# ESP32-Cam.net
KiCad netlist of a schematic drawn in Altium Designer
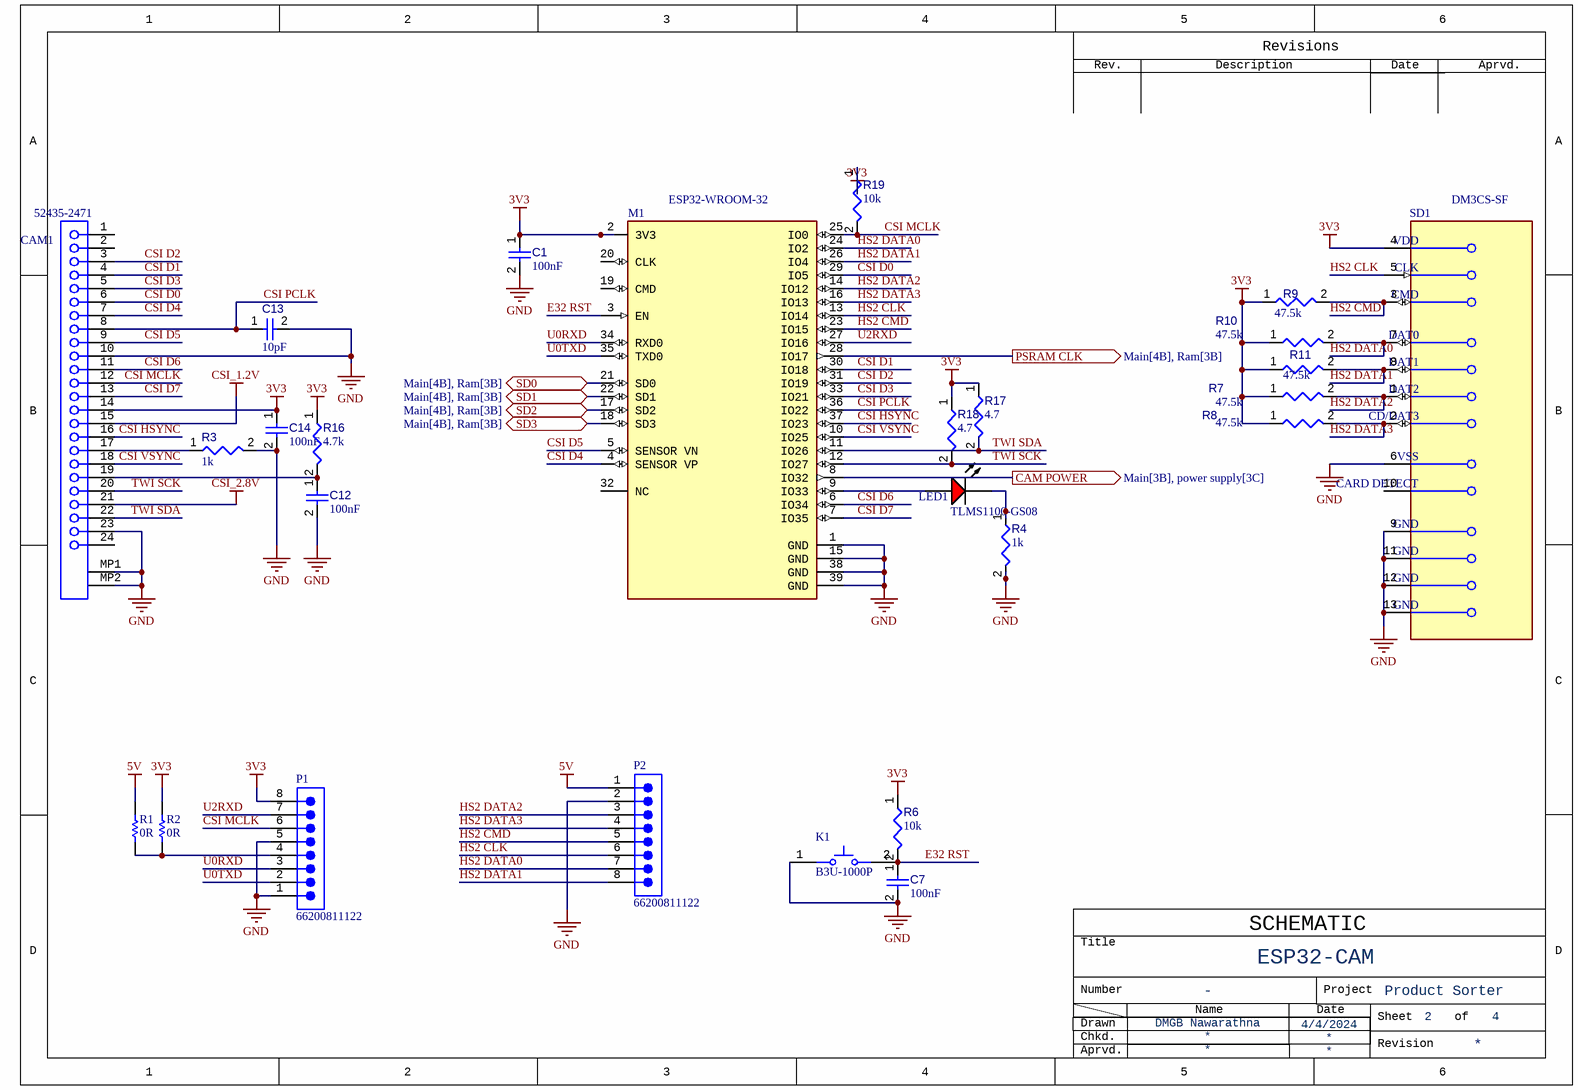
[diagram p0: ESP32-Cam.SchDoc]

(export (version "E")
  (design (tool "Eeschema 10.0.6"))
  (components
    (comp (ref "C1")
      (value "100nF")
      (footprint "CAPC1005X56X25LL10T15")
      (description "Chip Capacitor, 0.1 uF, +/- 5%, 16 V, 0402 (1005 Metric)")
      (fields (field (name "TOLERANCE") "5%") (field (name "Comment") "Capacitor 0.1 uF +/- 5% 16 V 0402"))
      (libsource (lib "Bimsara Nawarathna") (part "CAP-NP-2"))
    )
    (comp (ref "C7")
      (value "100nF")
      (footprint "CAPC1005X56X25LL10T15")
      (description "Chip Capacitor, 0.1 uF, +/- 5%, 16 V, 0402 (1005 Metric)")
      (fields (field (name "TOLERANCE") "5%") (field (name "Comment") "Capacitor 0.1 uF +/- 5% 16 V 0402"))
      (libsource (lib "Bimsara Nawarathna") (part "CAP-NP-2"))
    )
    (comp (ref "C12")
      (value "100nF")
      (footprint "CAPC1005X56X25LL10T15")
      (description "Chip Capacitor, 0.1 uF, +/- 5%, 16 V, 0402 (1005 Metric)")
      (fields (field (name "TOLERANCE") "5%") (field (name "Comment") "Capacitor 0.1 uF +/- 5% 16 V 0402"))
      (libsource (lib "Bimsara Nawarathna") (part "CAP-NP-2"))
    )
    (comp (ref "C13")
      (value "10pF")
      (footprint "CAPC1005X55X25ML05T05")
      (description "Chip Capacitor, 10 pF, +/- 5%, 50 V, 0402 (1005 Metric)")
      (fields (field (name "TOLERANCE") "5%") (field (name "Comment") "Capacitor 10 pF +/- 5% 50 V 0402"))
      (libsource (lib "Bimsara Nawarathna") (part "CAP-NP-2"))
    )
    (comp (ref "C14")
      (value "100nF")
      (footprint "CAPC1005X56X25LL10T15")
      (description "Chip Capacitor, 0.1 uF, +/- 5%, 16 V, 0402 (1005 Metric)")
      (fields (field (name "TOLERANCE") "5%") (field (name "Comment") "Capacitor 0.1 uF +/- 5% 16 V 0402"))
      (libsource (lib "Bimsara Nawarathna") (part "CAP-NP-2"))
    )
    (comp (ref "CAM1")
      (value "52435-2471")
      (footprint "MOLX-52435-2471")
      (fields (field (name "MANUFACTURER") "Molex"))
      (libsource (lib "Altium Content Vault") (part "MOLX-52435-2471"))
    )
    (comp (ref "K1")
      (value "B3U-1000P")
      (footprint "OMRON-B3U-1000_V")
      (description "Tactile Switch, SPST-NO, 0.05 A, 12 V, -25 to 70 degC, 2-Pin SMD, RoHS, Tape and Reel")
      (fields (field (name "MANUFACTURER") "Omron Electronic Components"))
      (libsource (lib "Bimsara Nawarathna") (part "SW-SPST-NO-2"))
    )
    (comp (ref "LED1")
      (value "TLMS1100-GS08")
      (footprint "VISH-TLMX1100_V")
      (description "Red Led, 20mA, 2.1 V, -40 to 100 degC, 2-Pin SMD (0603), RoHS, Tape and Reel")
      (fields (field (name "MANUFACTURER") "Vishay Semiconductor") (field (name "POWER") "90mW"))
      (libsource (lib "Bimsara Nawarathna") (part "LED-RED-AK-2"))
    )
    (comp (ref "M1")
      (value "ESP32-WROOM-32")
      (footprint "FP-ESP32-WROOM-32-MFG")
      (description "RX TXRX MOD WIFI SURFACE MOUNT")
      (libsource (lib "Altium Content Vault") (part "ee866abf0b6c51247b7f5cdebf2f250"))
    )
    (comp (ref "P1")
      (value "66200811122")
      (footprint "66200811122")
      (libsource (lib "Altium Content Vault") (part "Header_Male_1R_08P"))
    )
    (comp (ref "P2")
      (value "66200811122")
      (footprint "66200811122")
      (libsource (lib "Altium Content Vault") (part "Header_Male_1R_08P"))
    )
    (comp (ref "R1")
      (value "0R")
      (footprint "RESC1005X40X25ML05T10")
      (description "Chip Resistor, 0 Ohm, 0.063 W, -55 to 155 degC, 0402 (1005 Metric)")
      (fields (field (name "POWER") "63mW") (field (name "Comment") "Resistor 0R 0402 63 mW"))
      (libsource (lib "") (part "RES-2_1"))
    )
    (comp (ref "R2")
      (value "0R")
      (footprint "RESC1005X40X25ML05T10")
      (description "Chip Resistor, 0 Ohm, 0.063 W, -55 to 155 degC, 0402 (1005 Metric)")
      (fields (field (name "POWER") "63mW") (field (name "Comment") "Resistor 0R 0402 63 mW"))
      (libsource (lib "") (part "RES-2_1"))
    )
    (comp (ref "R3")
      (value "1k")
      (footprint "RESC0805(2012)_L")
      (description "Chip Resistor, 1 kOhms, +/-5%, 125 mW, -55 to 155 degC, 0805")
      (fields (field (name "TOLERANCE") "5%") (field (name "POWER") "125mW"))
      (libsource (lib "Bimsara Nawarathna") (part "RES-2"))
    )
    (comp (ref "R4")
      (value "1k")
      (footprint "RESC0805(2012)_L")
      (description "Chip Resistor, 1 kOhms, +/-5%, 125 mW, -55 to 155 degC, 0805")
      (fields (field (name "TOLERANCE") "5%") (field (name "POWER") "125mW"))
      (libsource (lib "Bimsara Nawarathna") (part "RES-2"))
    )
    (comp (ref "R6")
      (value "10k")
      (footprint "RESC0402(1005)_L")
      (description "Chip Resistor, 10 kOhms, +/-1 %, 63 mW, -55 to 125 degC, 0402")
      (fields (field (name "POWER") "63mW") (field (name "TOLERANCE") "1%"))
      (libsource (lib "Bimsara Nawarathna") (part "RES-2"))
    )
    (comp (ref "R7")
      (value "47.5k")
      (footprint "RESC0402(1005)_L")
      (description "Chip Resistor, 47,5 kOhms, +/-1 %, 63 mW, -55 to 155 degC, 0402")
      (fields (field (name "POWER") "63mW") (field (name "TOLERANCE") "1%"))
      (libsource (lib "Bimsara Nawarathna") (part "RES-2"))
    )
    (comp (ref "R8")
      (value "47.5k")
      (footprint "RESC0402(1005)_L")
      (description "Chip Resistor, 47,5 kOhms, +/-1 %, 63 mW, -55 to 155 degC, 0402")
      (fields (field (name "POWER") "63mW") (field (name "TOLERANCE") "1%"))
      (libsource (lib "Bimsara Nawarathna") (part "RES-2"))
    )
    (comp (ref "R9")
      (value "47.5k")
      (footprint "RESC0402(1005)_L")
      (description "Chip Resistor, 47,5 kOhms, +/-1 %, 63 mW, -55 to 155 degC, 0402")
      (fields (field (name "POWER") "63mW") (field (name "TOLERANCE") "1%"))
      (libsource (lib "Bimsara Nawarathna") (part "RES-2"))
    )
    (comp (ref "R10")
      (value "47.5k")
      (footprint "RESC0402(1005)_L")
      (description "Chip Resistor, 47,5 kOhms, +/-1 %, 63 mW, -55 to 155 degC, 0402")
      (fields (field (name "POWER") "63mW") (field (name "TOLERANCE") "1%"))
      (libsource (lib "Bimsara Nawarathna") (part "RES-2"))
    )
    (comp (ref "R11")
      (value "47.5k")
      (footprint "RESC0402(1005)_L")
      (description "Chip Resistor, 47,5 kOhms, +/-1 %, 63 mW, -55 to 155 degC, 0402")
      (fields (field (name "POWER") "63mW") (field (name "TOLERANCE") "1%"))
      (libsource (lib "Bimsara Nawarathna") (part "RES-2"))
    )
    (comp (ref "R16")
      (value "4.7k")
      (footprint "RESC1005X40X25ML05T05")
      (description "Chip Resistor, 4.7 KOhm, +/- 1%, 0.1 W, -55 to 155 degC, 0402 (1005 Metric)")
      (fields (field (name "POWER") "100mW") (field (name "TOLERANCE") "1%"))
      (libsource (lib "Bimsara Nawarathna") (part "RES-2"))
    )
    (comp (ref "R17")
      (value "4.7")
      (footprint "RESC0805(2012)_L")
      (description "Chip Resistor, 4,7 Ohms, +/-5 %, 125 mW, -55 to 155 degC, 0805")
      (fields (field (name "TOLERANCE") "5%") (field (name "POWER") "125mW"))
      (libsource (lib "Bimsara Nawarathna") (part "RES-2"))
    )
    (comp (ref "R18")
      (value "4.7")
      (footprint "RESC0805(2012)_L")
      (description "Chip Resistor, 4,7 Ohms, +/-5 %, 125 mW, -55 to 155 degC, 0805")
      (fields (field (name "TOLERANCE") "5%") (field (name "POWER") "125mW"))
      (libsource (lib "Bimsara Nawarathna") (part "RES-2"))
    )
    (comp (ref "R19")
      (value "10k")
      (footprint "RESC2013X50X35ML15T15")
      (description "Chip Resistor, 10 KOhm, +/- 1%, 125 mW, -55 to 155 degC, 0805 (2012 Metric)")
      (fields (field (name "TOLERANCE") "1%") (field (name "POWER") "125mW"))
      (libsource (lib "Bimsara Nawarathna") (part "RES-2"))
    )
    (comp (ref "SD1")
      (value "DM3CS-SF")
      (footprint "FP-DM3CS-SF-MFG")
      (description "CONN MICRO SD CARD HINGED TYPE")
      (libsource (lib "Altium Content Vault") (part "bac915de5305cfdd1ca301aae530106"))
    )
  )
  (nets
    (net (code "1") (name "/CAM POWER") (class "Default")
      (node (ref "M1") (pin "8") (pinfunction "IO32_8") (pintype "output"))
    )
    (net (code "2") (name "/CSI D0") (class "Default")
      (node (ref "CAM1") (pin "6") (pinfunction "6_6") (pintype "passive"))
      (node (ref "M1") (pin "29") (pinfunction "IO5_29") (pintype "bidirectional"))
    )
    (net (code "3") (name "/CSI D1") (class "Default")
      (node (ref "CAM1") (pin "4") (pinfunction "4_4") (pintype "passive"))
      (node (ref "M1") (pin "30") (pinfunction "IO18_30") (pintype "bidirectional"))
    )
    (net (code "4") (name "/CSI D2") (class "Default")
      (node (ref "CAM1") (pin "3") (pinfunction "3_3") (pintype "passive"))
      (node (ref "M1") (pin "31") (pinfunction "IO19_31") (pintype "bidirectional"))
    )
    (net (code "5") (name "/CSI D3") (class "Default")
      (node (ref "CAM1") (pin "5") (pinfunction "5_5") (pintype "passive"))
      (node (ref "M1") (pin "33") (pinfunction "IO21_33") (pintype "bidirectional"))
    )
    (net (code "6") (name "/CSI D4") (class "Default")
      (node (ref "CAM1") (pin "7") (pinfunction "7_7") (pintype "passive"))
      (node (ref "M1") (pin "4") (pinfunction "SENSOR_VP_4") (pintype "bidirectional"))
    )
    (net (code "7") (name "/CSI D5") (class "Default")
      (node (ref "CAM1") (pin "9") (pinfunction "9_9") (pintype "passive"))
      (node (ref "M1") (pin "5") (pinfunction "SENSOR_VN_5") (pintype "bidirectional"))
    )
    (net (code "8") (name "/CSI D6") (class "Default")
      (node (ref "CAM1") (pin "11") (pinfunction "11_11") (pintype "passive"))
      (node (ref "M1") (pin "6") (pinfunction "IO34_6") (pintype "bidirectional"))
    )
    (net (code "9") (name "/CSI D7") (class "Default")
      (node (ref "CAM1") (pin "13") (pinfunction "13_13") (pintype "passive"))
      (node (ref "M1") (pin "7") (pinfunction "IO35_7") (pintype "bidirectional"))
    )
    (net (code "10") (name "/CSI HSYNC") (class "Default")
      (node (ref "CAM1") (pin "16") (pinfunction "16_16") (pintype "passive"))
      (node (ref "M1") (pin "37") (pinfunction "IO23_37") (pintype "bidirectional"))
    )
    (net (code "11") (name "/CSI MCLK") (class "Default")
      (node (ref "CAM1") (pin "12") (pinfunction "12_12") (pintype "passive"))
      (node (ref "M1") (pin "25") (pinfunction "IO0_25") (pintype "bidirectional"))
      (node (ref "P1") (pin "6") (pinfunction "6_6") (pintype "passive"))
      (node (ref "R19") (pin "2") (pinfunction "2_2") (pintype "passive"))
    )
    (net (code "12") (name "/CSI PCLK") (class "Default")
      (node (ref "C13") (pin "1") (pinfunction "1_1") (pintype "passive"))
      (node (ref "CAM1") (pin "8") (pinfunction "8_8") (pintype "passive"))
      (node (ref "M1") (pin "36") (pinfunction "IO22_36") (pintype "bidirectional"))
    )
    (net (code "13") (name "/CSI VSYNC") (class "Default")
      (node (ref "CAM1") (pin "18") (pinfunction "18_18") (pintype "passive"))
      (node (ref "M1") (pin "10") (pinfunction "IO25_10") (pintype "bidirectional"))
    )
    (net (code "14") (name "/E32 RST") (class "Default")
      (node (ref "C7") (pin "1") (pinfunction "1_1") (pintype "passive"))
      (node (ref "K1") (pin "2") (pinfunction "2_2") (pintype "passive"))
      (node (ref "M1") (pin "3") (pinfunction "EN_3") (pintype "input"))
      (node (ref "R6") (pin "2") (pinfunction "2_2") (pintype "passive"))
    )
    (net (code "15") (name "/HS2 CLK") (class "Default")
      (node (ref "M1") (pin "13") (pinfunction "IO14_13") (pintype "bidirectional"))
      (node (ref "P2") (pin "6") (pinfunction "6_6") (pintype "passive"))
      (node (ref "SD1") (pin "5") (pinfunction "CLK_5") (pintype "input"))
    )
    (net (code "16") (name "/HS2 CMD") (class "Default")
      (node (ref "M1") (pin "23") (pinfunction "IO15_23") (pintype "bidirectional"))
      (node (ref "P2") (pin "5") (pinfunction "5_5") (pintype "passive"))
      (node (ref "R9") (pin "2") (pinfunction "2_2") (pintype "passive"))
      (node (ref "SD1") (pin "3") (pinfunction "CMD_3") (pintype "bidirectional"))
    )
    (net (code "17") (name "/HS2 DATA0") (class "Default")
      (node (ref "M1") (pin "24") (pinfunction "IO2_24") (pintype "bidirectional"))
      (node (ref "P2") (pin "7") (pinfunction "7_7") (pintype "passive"))
      (node (ref "R10") (pin "2") (pinfunction "2_2") (pintype "passive"))
      (node (ref "SD1") (pin "7") (pinfunction "DAT0_7") (pintype "bidirectional"))
    )
    (net (code "18") (name "/HS2 DATA1") (class "Default")
      (node (ref "M1") (pin "26") (pinfunction "IO4_26") (pintype "bidirectional"))
      (node (ref "P2") (pin "8") (pinfunction "8_8") (pintype "passive"))
      (node (ref "R11") (pin "2") (pinfunction "2_2") (pintype "passive"))
      (node (ref "SD1") (pin "8") (pinfunction "DAT1_8") (pintype "bidirectional"))
    )
    (net (code "19") (name "/HS2 DATA2") (class "Default")
      (node (ref "M1") (pin "14") (pinfunction "IO12_14") (pintype "bidirectional"))
      (node (ref "P2") (pin "3") (pinfunction "3_3") (pintype "passive"))
      (node (ref "R7") (pin "2") (pinfunction "2_2") (pintype "passive"))
      (node (ref "SD1") (pin "1") (pinfunction "DAT2_1") (pintype "bidirectional"))
    )
    (net (code "20") (name "/HS2 DATA3") (class "Default")
      (node (ref "M1") (pin "16") (pinfunction "IO13_16") (pintype "bidirectional"))
      (node (ref "P2") (pin "4") (pinfunction "4_4") (pintype "passive"))
      (node (ref "R8") (pin "2") (pinfunction "2_2") (pintype "passive"))
      (node (ref "SD1") (pin "2") (pinfunction "CD/DAT3_2") (pintype "bidirectional"))
    )
    (net (code "21") (name "/PSRAM CLK") (class "Default")
      (node (ref "M1") (pin "28") (pinfunction "IO17_28") (pintype "output"))
    )
    (net (code "22") (name "/SD0") (class "Default")
      (node (ref "M1") (pin "21") (pinfunction "SD0_21") (pintype "bidirectional"))
    )
    (net (code "23") (name "/SD1") (class "Default")
      (node (ref "M1") (pin "22") (pinfunction "SD1_22") (pintype "bidirectional"))
    )
    (net (code "24") (name "/SD2") (class "Default")
      (node (ref "M1") (pin "17") (pinfunction "SD2_17") (pintype "bidirectional"))
    )
    (net (code "25") (name "/SD3") (class "Default")
      (node (ref "M1") (pin "18") (pinfunction "SD3_18") (pintype "bidirectional"))
    )
    (net (code "26") (name "/TWI SCK") (class "Default")
      (node (ref "CAM1") (pin "20") (pinfunction "20_20") (pintype "passive"))
      (node (ref "M1") (pin "12") (pinfunction "IO27_12") (pintype "bidirectional"))
      (node (ref "R18") (pin "2") (pinfunction "2_2") (pintype "passive"))
    )
    (net (code "27") (name "/TWI SDA") (class "Default")
      (node (ref "CAM1") (pin "22") (pinfunction "22_22") (pintype "passive"))
      (node (ref "M1") (pin "11") (pinfunction "IO26_11") (pintype "bidirectional"))
      (node (ref "R17") (pin "2") (pinfunction "2_2") (pintype "passive"))
    )
    (net (code "28") (name "/U0RXD") (class "Default")
      (node (ref "M1") (pin "34") (pinfunction "RXD0_34") (pintype "bidirectional"))
      (node (ref "P1") (pin "3") (pinfunction "3_3") (pintype "passive"))
    )
    (net (code "29") (name "/U0TXD") (class "Default")
      (node (ref "M1") (pin "35") (pinfunction "TXD0_35") (pintype "bidirectional"))
      (node (ref "P1") (pin "2") (pinfunction "2_2") (pintype "passive"))
    )
    (net (code "30") (name "/U2RXD") (class "Default")
      (node (ref "M1") (pin "27") (pinfunction "IO16_27") (pintype "bidirectional"))
      (node (ref "P1") (pin "7") (pinfunction "7_7") (pintype "passive"))
    )
    (net (code "31") (name "3V3") (class "Default")
      (node (ref "C1") (pin "1") (pinfunction "1_1") (pintype "passive"))
      (node (ref "C14") (pin "1") (pinfunction "1_1") (pintype "passive"))
      (node (ref "CAM1") (pin "14") (pinfunction "14_14") (pintype "passive"))
      (node (ref "M1") (pin "2") (pinfunction "3V3_2") (pintype "power_in"))
      (node (ref "P1") (pin "8") (pinfunction "8_8") (pintype "passive"))
      (node (ref "R10") (pin "1") (pinfunction "1_1") (pintype "passive"))
      (node (ref "R11") (pin "1") (pinfunction "1_1") (pintype "passive"))
      (node (ref "R16") (pin "1") (pinfunction "1_1") (pintype "passive"))
      (node (ref "R17") (pin "1") (pinfunction "1_1") (pintype "passive"))
      (node (ref "R18") (pin "1") (pinfunction "1_1") (pintype "passive"))
      (node (ref "R19") (pin "1") (pinfunction "1_1") (pintype "passive"))
      (node (ref "R2") (pin "1") (pinfunction "1_1") (pintype "passive"))
      (node (ref "R6") (pin "1") (pinfunction "1_1") (pintype "passive"))
      (node (ref "R7") (pin "1") (pinfunction "1_1") (pintype "passive"))
      (node (ref "R8") (pin "1") (pinfunction "1_1") (pintype "passive"))
      (node (ref "R9") (pin "1") (pinfunction "1_1") (pintype "passive"))
      (node (ref "SD1") (pin "4") (pinfunction "VDD_4") (pintype "power_in"))
    )
    (net (code "32") (name "5V") (class "Default")
      (node (ref "P2") (pin "1") (pinfunction "1_1") (pintype "passive"))
      (node (ref "R1") (pin "1") (pinfunction "1_1") (pintype "passive"))
    )
    (net (code "33") (name "CSI_1.2V") (class "Default")
      (node (ref "CAM1") (pin "15") (pinfunction "15_15") (pintype "passive"))
    )
    (net (code "34") (name "CSI_2.8V") (class "Default")
      (node (ref "CAM1") (pin "21") (pinfunction "21_21") (pintype "passive"))
    )
    (net (code "35") (name "GND") (class "Default")
      (node (ref "C1") (pin "2") (pinfunction "2_2") (pintype "passive"))
      (node (ref "C12") (pin "2") (pinfunction "2_2") (pintype "passive"))
      (node (ref "C13") (pin "2") (pinfunction "2_2") (pintype "passive"))
      (node (ref "C14") (pin "2") (pinfunction "2_2") (pintype "passive"))
      (node (ref "C7") (pin "2") (pinfunction "2_2") (pintype "passive"))
      (node (ref "CAM1") (pin "10") (pinfunction "10_10") (pintype "passive"))
      (node (ref "CAM1") (pin "23") (pinfunction "23_23") (pintype "passive"))
      (node (ref "CAM1") (pin "MP1") (pinfunction "MP1_MP1") (pintype "passive"))
      (node (ref "CAM1") (pin "MP2") (pinfunction "MP2_MP2") (pintype "passive"))
      (node (ref "K1") (pin "1") (pinfunction "1_1") (pintype "passive"))
      (node (ref "M1") (pin "1") (pinfunction "GND_1") (pintype "power_in"))
      (node (ref "M1") (pin "15") (pinfunction "GND_15") (pintype "power_in"))
      (node (ref "M1") (pin "38") (pinfunction "GND_38") (pintype "power_in"))
      (node (ref "M1") (pin "39") (pinfunction "GND_39") (pintype "power_in"))
      (node (ref "P1") (pin "1") (pinfunction "1_1") (pintype "passive"))
      (node (ref "P1") (pin "5") (pinfunction "5_5") (pintype "passive"))
      (node (ref "P2") (pin "2") (pinfunction "2_2") (pintype "passive"))
      (node (ref "R3") (pin "2") (pinfunction "2_2") (pintype "passive"))
      (node (ref "R4") (pin "2") (pinfunction "2_2") (pintype "passive"))
      (node (ref "SD1") (pin "11") (pinfunction "GND_11") (pintype "power_in"))
      (node (ref "SD1") (pin "12") (pinfunction "GND_12") (pintype "power_in"))
      (node (ref "SD1") (pin "13") (pinfunction "GND_13") (pintype "power_in"))
      (node (ref "SD1") (pin "6") (pinfunction "VSS_6") (pintype "power_in"))
      (node (ref "SD1") (pin "9") (pinfunction "GND_9") (pintype "power_in"))
    )
    (net (code "36") (name "Net-(C12-Pad1)") (class "Default")
      (node (ref "C12") (pin "1") (pinfunction "1_1") (pintype "passive"))
      (node (ref "CAM1") (pin "19") (pinfunction "19_19") (pintype "passive"))
      (node (ref "R16") (pin "2") (pinfunction "2_2") (pintype "passive"))
    )
    (net (code "37") (name "Net-(CAM1-Pad17)") (class "Default")
      (node (ref "CAM1") (pin "17") (pinfunction "17_17") (pintype "passive"))
      (node (ref "R3") (pin "1") (pinfunction "1_1") (pintype "passive"))
    )
    (net (code "38") (name "Net-(LED1-A)") (class "Default")
      (node (ref "LED1") (pin "1") (pinfunction "A_1") (pintype "passive"))
      (node (ref "M1") (pin "9") (pinfunction "IO33_9") (pintype "bidirectional"))
    )
    (net (code "39") (name "Net-(LED1-K)") (class "Default")
      (node (ref "LED1") (pin "2") (pinfunction "K_2") (pintype "passive"))
      (node (ref "R4") (pin "1") (pinfunction "1_1") (pintype "passive"))
    )
    (net (code "40") (name "Net-(P1-Pad4)") (class "Default")
      (node (ref "P1") (pin "4") (pinfunction "4_4") (pintype "passive"))
      (node (ref "R1") (pin "2") (pinfunction "2_2") (pintype "passive"))
      (node (ref "R2") (pin "2") (pinfunction "2_2") (pintype "passive"))
    )
    (net (code "41") (name "unconnected-(CAM1-Pad1)") (class "Default")
      (node (ref "CAM1") (pin "1") (pinfunction "1_1") (pintype "passive"))
    )
    (net (code "42") (name "unconnected-(CAM1-Pad2)") (class "Default")
      (node (ref "CAM1") (pin "2") (pinfunction "2_2") (pintype "passive"))
    )
    (net (code "43") (name "unconnected-(CAM1-Pad24)") (class "Default")
      (node (ref "CAM1") (pin "24") (pinfunction "24_24") (pintype "passive"))
    )
    (net (code "44") (name "unconnected-(M1-CLK-Pad20)") (class "Default")
      (node (ref "M1") (pin "20") (pinfunction "CLK_20") (pintype "bidirectional"))
    )
    (net (code "45") (name "unconnected-(M1-CMD-Pad19)") (class "Default")
      (node (ref "M1") (pin "19") (pinfunction "CMD_19") (pintype "bidirectional"))
    )
    (net (code "46") (name "unconnected-(M1-NC-Pad32)") (class "Default")
      (node (ref "M1") (pin "32") (pinfunction "NC_32") (pintype "passive"))
    )
    (net (code "47") (name "unconnected-(SD1-CARD_DETECT-Pad10)") (class "Default")
      (node (ref "SD1") (pin "10") (pinfunction "CARD_DETECT_10") (pintype "passive"))
    )
  )
)
